# TinyDev.net
KiCad netlist of a schematic drawn in EAGLE
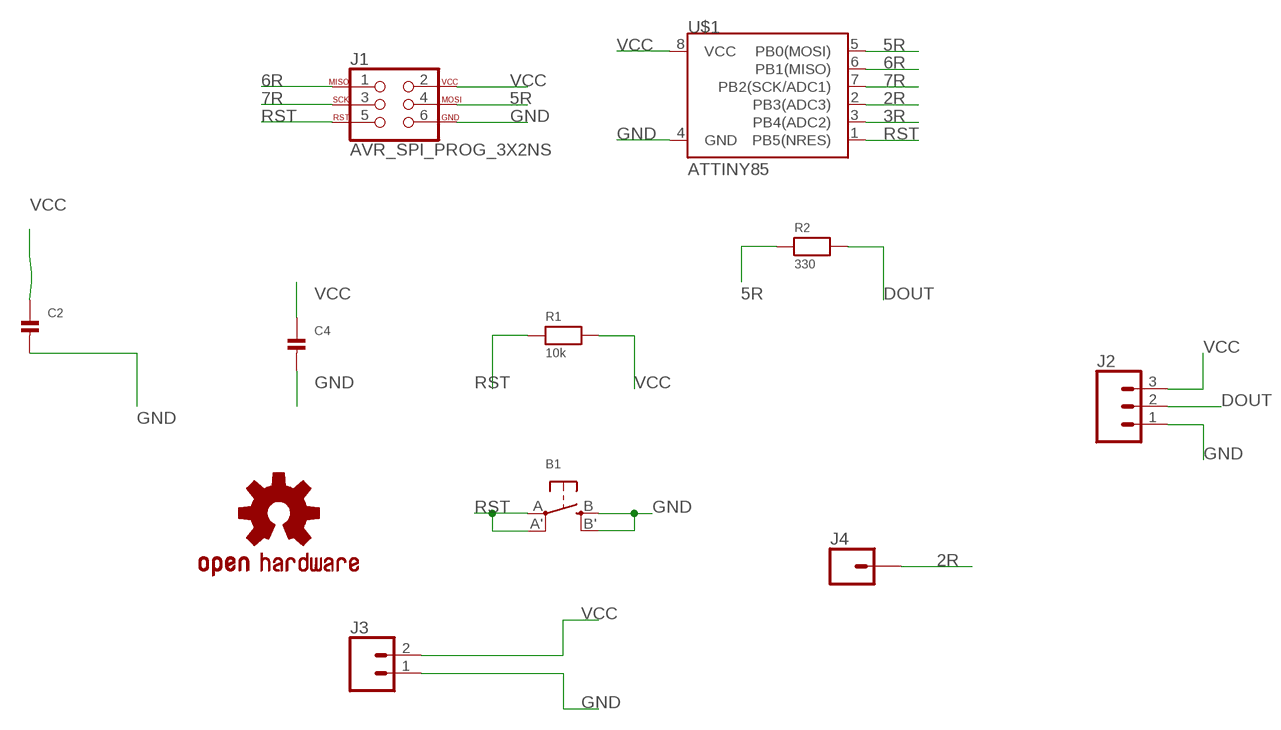
[diagram p0: schematic, sheet 1]

(export (version "E")
  (design (tool "Eeschema 10.0.6"))
  (components
    (comp (ref "B1")
      (value "SWITCH_TACT_SMT4.6X2.8")
      (footprint "eagle-import:BTN_KMR2_4.6X2.8")
      (libsource (lib "eagle-import") (part "SWITCH_TACT_SMT4.6X2.8"))
    )
    (comp (ref "C2")
      (value "CAP_CERAMIC_0805")
      (footprint "eagle-import:_0805")
      (libsource (lib "eagle-import") (part "CAP_CERAMIC_0805"))
    )
    (comp (ref "C4")
      (value "CAP_CERAMIC_0805")
      (footprint "eagle-import:_0805")
      (libsource (lib "eagle-import") (part "CAP_CERAMIC_0805"))
    )
    (comp (ref "J1")
      (value "AVR_SPI_PROG_3X2NS")
      (footprint "eagle-import:2X3-NS")
      (libsource (lib "eagle-import") (part "AVR_SPI_PROG_3X2NS"))
    )
    (comp (ref "J2")
      (value "CONN_031X03_NO_SILK")
      (footprint "eagle-import:1X03_NO_SILK")
      (libsource (lib "eagle-import") (part "CONN_031X03_NO_SILK"))
    )
    (comp (ref "J3")
      (value "CONN_021X02_NO_SILK")
      (footprint "eagle-import:1X02_NO_SILK")
      (libsource (lib "eagle-import") (part "CONN_021X02_NO_SILK"))
    )
    (comp (ref "J4")
      (value "CONN_01PTH_NO_SILK_KIT")
      (footprint "eagle-import:1X01NS_KIT")
      (libsource (lib "eagle-import") (part "CONN_01PTH_NO_SILK_KIT"))
    )
    (comp (ref "LOGO1")
      (value "OSHW-LOGOS")
      (footprint "eagle-import:OSHW-LOGO-S")
      (libsource (lib "eagle-import") (part "OSHW-LOGOS"))
    )
    (comp (ref "R1")
      (value "10k")
      (footprint "eagle-import:0603-MINI")
      (libsource (lib "eagle-import") (part "RESISTOR0603MINI"))
    )
    (comp (ref "R2")
      (value "330")
      (footprint "eagle-import:0603-MINI")
      (libsource (lib "eagle-import") (part "RESISTOR0603MINI"))
    )
    (comp (ref "U$1")
      (value "ATTINY85")
      (footprint "eagle-import:SO08-EIAJ")
      (libsource (lib "eagle-import") (part "ATTINY45"))
    )
  )
  (nets
    (net (code "1") (name "/2R") (class "Default")
      (node (ref "J4") (pin "1") (pinfunction "1_1") (pintype "passive"))
      (node (ref "U$1") (pin "2") (pinfunction "PB3(ADC3)_2") (pintype "bidirectional"))
    )
    (net (code "2") (name "/3R") (class "Default")
      (node (ref "U$1") (pin "3") (pinfunction "PB4(ADC2)_3") (pintype "bidirectional"))
    )
    (net (code "3") (name "/5R") (class "Default")
      (node (ref "J1") (pin "4") (pinfunction "4_4") (pintype "passive"))
      (node (ref "R2") (pin "1") (pinfunction "1_1") (pintype "passive"))
      (node (ref "U$1") (pin "5") (pinfunction "PB0(MOSI)_5") (pintype "bidirectional"))
    )
    (net (code "4") (name "/6R") (class "Default")
      (node (ref "J1") (pin "1") (pinfunction "1_1") (pintype "passive"))
      (node (ref "U$1") (pin "6") (pinfunction "PB1(MISO)_6") (pintype "bidirectional"))
    )
    (net (code "5") (name "/7R") (class "Default")
      (node (ref "J1") (pin "3") (pinfunction "3_3") (pintype "passive"))
      (node (ref "U$1") (pin "7") (pinfunction "PB2(SCK/ADC1)_7") (pintype "bidirectional"))
    )
    (net (code "6") (name "/DOUT") (class "Default")
      (node (ref "J2") (pin "2") (pinfunction "2_2") (pintype "passive"))
      (node (ref "R2") (pin "2") (pinfunction "2_2") (pintype "passive"))
    )
    (net (code "7") (name "/GND") (class "Default")
      (node (ref "B1") (pin "B") (pinfunction "S_B") (pintype "passive"))
      (node (ref "B1") (pin "B'") (pinfunction "S1_B'") (pintype "passive"))
      (node (ref "C2") (pin "2") (pinfunction "P$2_2") (pintype "passive"))
      (node (ref "C4") (pin "2") (pinfunction "P$2_2") (pintype "passive"))
      (node (ref "J1") (pin "6") (pinfunction "6_6") (pintype "passive"))
      (node (ref "J2") (pin "1") (pinfunction "1_1") (pintype "passive"))
      (node (ref "J3") (pin "1") (pinfunction "1_1") (pintype "passive"))
      (node (ref "U$1") (pin "4") (pinfunction "GND_4") (pintype "bidirectional"))
    )
    (net (code "8") (name "/RST") (class "Default")
      (node (ref "B1") (pin "A") (pinfunction "P_A") (pintype "passive"))
      (node (ref "B1") (pin "A'") (pinfunction "P1_A'") (pintype "passive"))
      (node (ref "J1") (pin "5") (pinfunction "5_5") (pintype "passive"))
      (node (ref "R1") (pin "1") (pinfunction "1_1") (pintype "passive"))
      (node (ref "U$1") (pin "1") (pinfunction "PB5(NRES)_1") (pintype "bidirectional"))
    )
    (net (code "9") (name "/VCC") (class "Default")
      (node (ref "C2") (pin "1") (pinfunction "P$1_1") (pintype "passive"))
      (node (ref "C4") (pin "1") (pinfunction "P$1_1") (pintype "passive"))
      (node (ref "J1") (pin "2") (pinfunction "2_2") (pintype "passive"))
      (node (ref "J2") (pin "3") (pinfunction "3_3") (pintype "passive"))
      (node (ref "J3") (pin "2") (pinfunction "2_2") (pintype "passive"))
      (node (ref "R1") (pin "2") (pinfunction "2_2") (pintype "passive"))
      (node (ref "U$1") (pin "8") (pinfunction "VCC_8") (pintype "bidirectional"))
    )
  )
)
